# Flasher_LED_Board.net
KiCad netlist of a schematic drawn in EAGLE
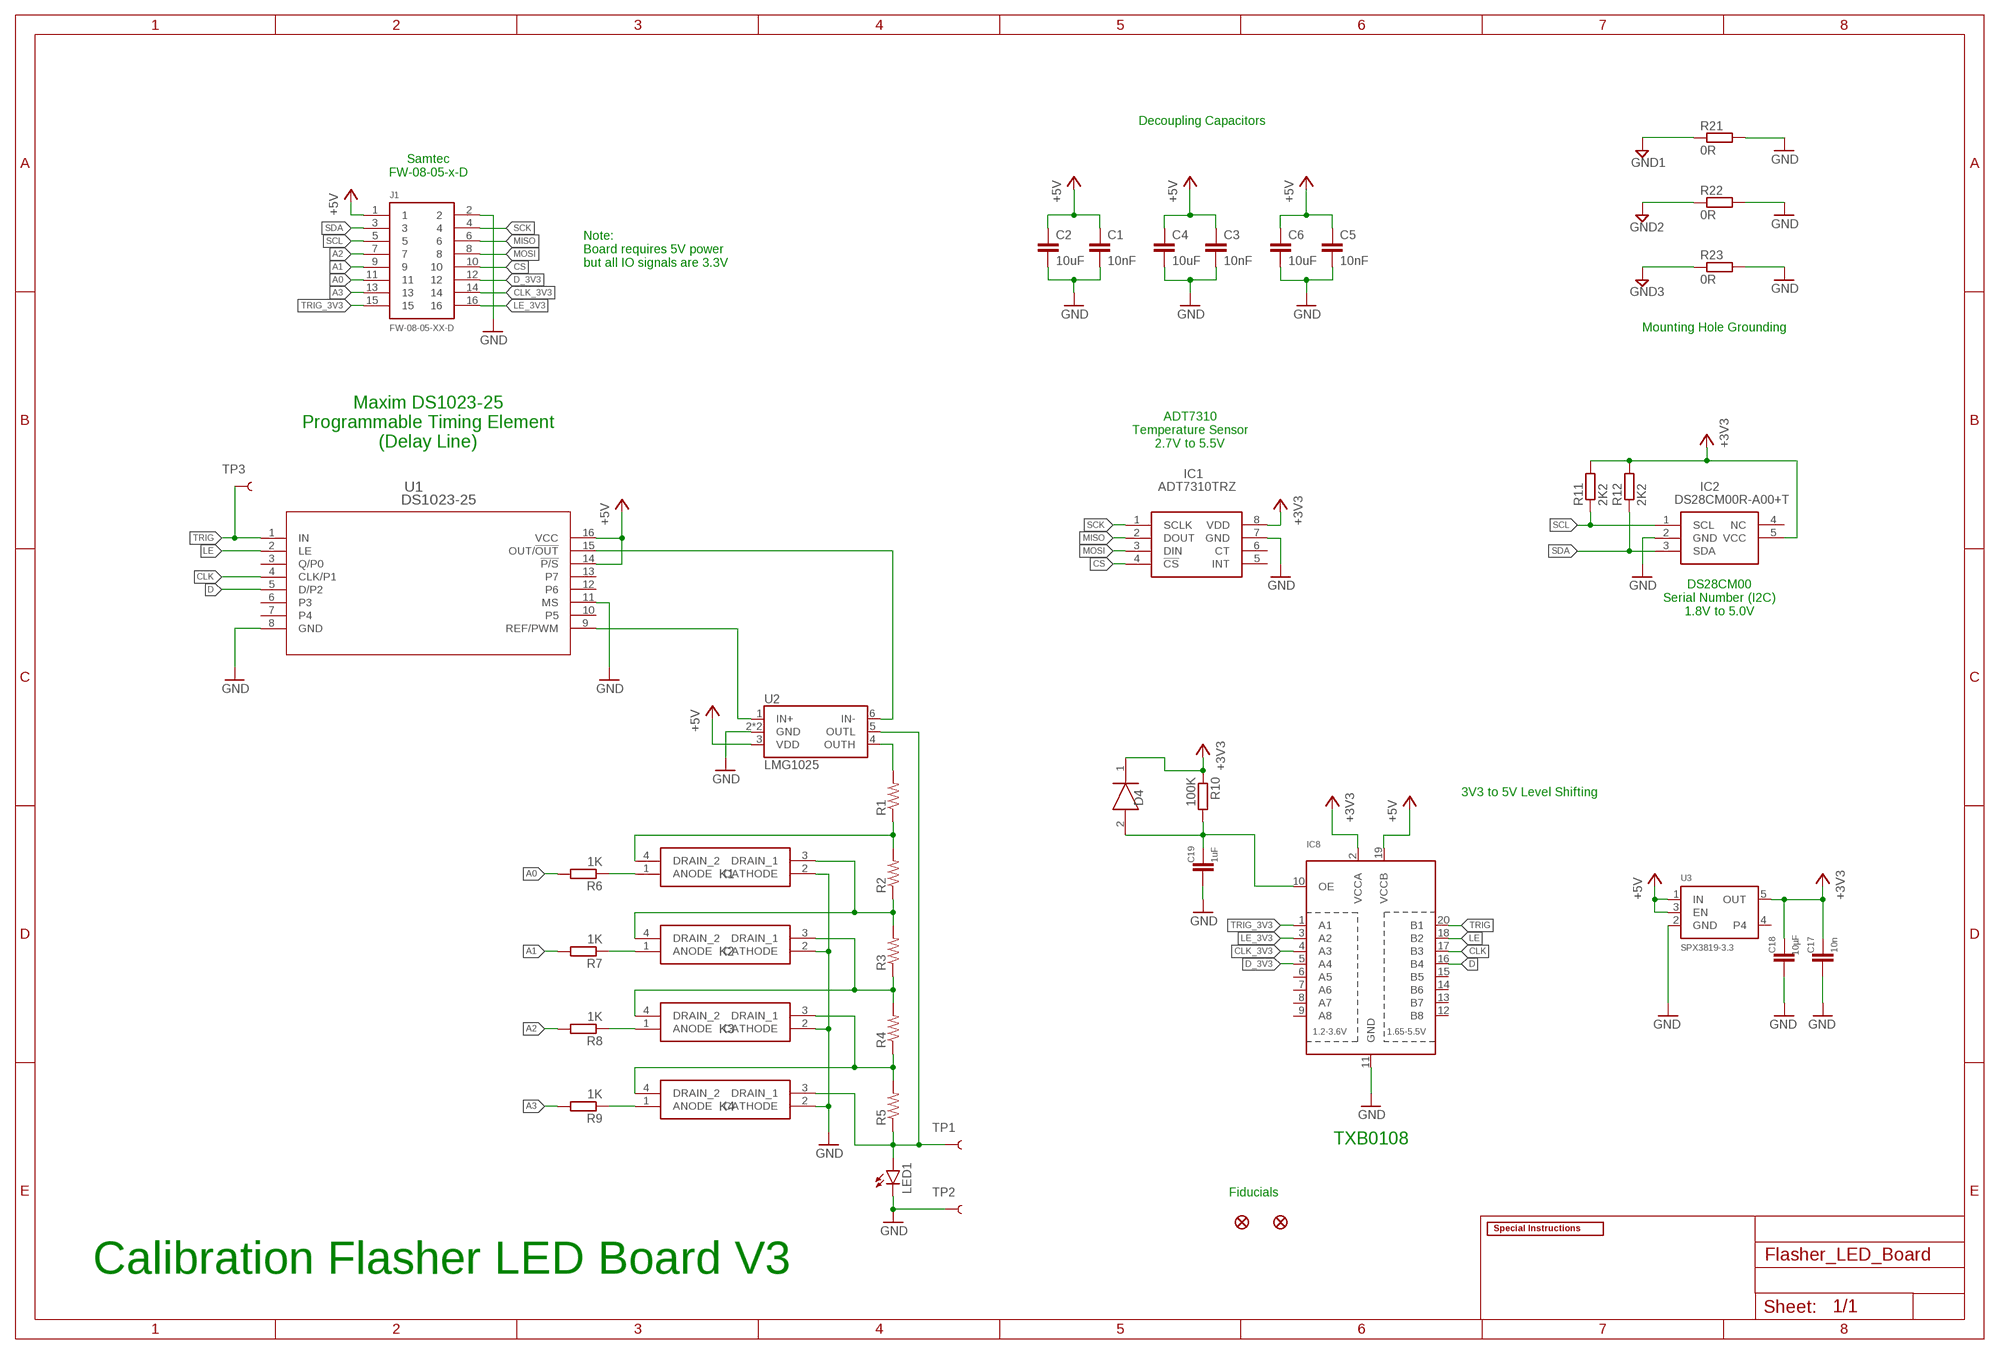
[diagram p0: schematic, sheet 1]

(export (version "E")
  (design (tool "Eeschema 10.0.6"))
  (components
    (comp (ref "C1")
      (value "10nF")
      (footprint "eagle-import:C0805")
      (libsource (lib "eagle-import") (part "C-EUC0805"))
    )
    (comp (ref "C2")
      (value "10uF")
      (footprint "eagle-import:C0805")
      (libsource (lib "eagle-import") (part "C-EUC0805"))
    )
    (comp (ref "C3")
      (value "10nF")
      (footprint "eagle-import:C0805")
      (libsource (lib "eagle-import") (part "C-EUC0805"))
    )
    (comp (ref "C4")
      (value "10uF")
      (footprint "eagle-import:C0805")
      (libsource (lib "eagle-import") (part "C-EUC0805"))
    )
    (comp (ref "C5")
      (value "10nF")
      (footprint "eagle-import:C0805")
      (libsource (lib "eagle-import") (part "C-EUC0805"))
    )
    (comp (ref "C6")
      (value "10uF")
      (footprint "eagle-import:C0805")
      (libsource (lib "eagle-import") (part "C-EUC0805"))
    )
    (comp (ref "C17")
      (value "10n")
      (footprint "eagle-import:C0603")
      (libsource (lib "eagle-import") (part "C-EUC0603"))
    )
    (comp (ref "C18")
      (value "10µF")
      (footprint "eagle-import:C0805")
      (libsource (lib "eagle-import") (part "C-EUC0805"))
    )
    (comp (ref "C19")
      (value "1uF")
      (footprint "eagle-import:C0603")
      (libsource (lib "eagle-import") (part "C-EUC0603"))
    )
    (comp (ref "D4")
      (value "CD0603-B00340")
      (footprint "eagle-import:DIOM179X85N")
      (libsource (lib "eagle-import") (part "CD0603-B00340"))
    )
    (comp (ref "FD1")
      (value "FIDUCIAL1X2")
      (footprint "eagle-import:FIDUCIAL-1X2")
      (libsource (lib "eagle-import") (part "FIDUCIAL1X2"))
    )
    (comp (ref "FD2")
      (value "FIDUCIAL1X2")
      (footprint "eagle-import:FIDUCIAL-1X2")
      (libsource (lib "eagle-import") (part "FIDUCIAL1X2"))
    )
    (comp (ref "IC1")
      (value "ADT7310TRZ")
      (footprint "eagle-import:SOIC127P600X175-8N")
      (fields (field (name "RS_PART_NUMBER") "7969022P"))
      (libsource (lib "eagle-import") (part "ADT7310TRZ"))
    )
    (comp (ref "IC2")
      (value "DS28CM00R-A00+T")
      (footprint "eagle-import:SOT95P280X145-5N")
      (fields (field (name "MOUSER_PART_NUMBER") "700-DS28CM00R-A00T"))
      (libsource (lib "eagle-import") (part "DS28CM00R-A00+T"))
    )
    (comp (ref "IC8")
      (value "TXB0108PWR")
      (footprint "eagle-import:TSSOP20")
      (libsource (lib "eagle-import") (part "TXB0108PWR"))
    )
    (comp (ref "J1")
      (value "FW-08-05-XX-D")
      (footprint "eagle-import:FW-08-05-XX-D")
      (libsource (lib "eagle-import") (part "FW-08-05-XX-D"))
    )
    (comp (ref "K1")
      (value "TLP3475R(TP,F")
      (footprint "eagle-import:TLP3475RTPF")
      (fields (field (name "MOUSER_PART_NUMBER") "757-TLP3475RTPF"))
      (libsource (lib "eagle-import") (part "TLP3475R(TP,F"))
    )
    (comp (ref "K2")
      (value "TLP3475R(TP,F")
      (footprint "eagle-import:TLP3475RTPF")
      (fields (field (name "MOUSER_PART_NUMBER") "757-TLP3475RTPF"))
      (libsource (lib "eagle-import") (part "TLP3475R(TP,F"))
    )
    (comp (ref "K3")
      (value "TLP3475R(TP,F")
      (footprint "eagle-import:TLP3475RTPF")
      (fields (field (name "MOUSER_PART_NUMBER") "757-TLP3475RTPF"))
      (libsource (lib "eagle-import") (part "TLP3475R(TP,F"))
    )
    (comp (ref "K4")
      (value "TLP3475R(TP,F")
      (footprint "eagle-import:TLP3475RTPF")
      (fields (field (name "MOUSER_PART_NUMBER") "757-TLP3475RTPF"))
      (libsource (lib "eagle-import") (part "TLP3475R(TP,F"))
    )
    (comp (ref "LED1")
      (value "LED3MM")
      (footprint "eagle-import:LED3MM")
      (libsource (lib "eagle-import") (part "LED3MM"))
    )
    (comp (ref "LOGO6")
      (value "SPECIAL_INSTRUCTIONS-ORDERING")
      (footprint "eagle-import:ORDERING_INSTRUCTIONS")
      (libsource (lib "eagle-import") (part "SPECIAL_INSTRUCTIONS-ORDERING"))
    )
    (comp (ref "R1")
      (value "RESISTOR0805-RES")
      (footprint "eagle-import:0805")
      (libsource (lib "eagle-import") (part "RESISTOR0805-RES"))
    )
    (comp (ref "R2")
      (value "RESISTOR0805-RES")
      (footprint "eagle-import:0805")
      (libsource (lib "eagle-import") (part "RESISTOR0805-RES"))
    )
    (comp (ref "R3")
      (value "RESISTOR0805-RES")
      (footprint "eagle-import:0805")
      (libsource (lib "eagle-import") (part "RESISTOR0805-RES"))
    )
    (comp (ref "R4")
      (value "RESISTOR0805-RES")
      (footprint "eagle-import:0805")
      (libsource (lib "eagle-import") (part "RESISTOR0805-RES"))
    )
    (comp (ref "R5")
      (value "RESISTOR0805-RES")
      (footprint "eagle-import:0805")
      (libsource (lib "eagle-import") (part "RESISTOR0805-RES"))
    )
    (comp (ref "R6")
      (value "1K")
      (footprint "eagle-import:R0603")
      (libsource (lib "eagle-import") (part "resistor_348_R-EU_R0603"))
    )
    (comp (ref "R7")
      (value "1K")
      (footprint "eagle-import:R0603")
      (libsource (lib "eagle-import") (part "resistor_348_R-EU_R0603"))
    )
    (comp (ref "R8")
      (value "1K")
      (footprint "eagle-import:R0603")
      (libsource (lib "eagle-import") (part "resistor_348_R-EU_R0603"))
    )
    (comp (ref "R9")
      (value "1K")
      (footprint "eagle-import:R0603")
      (libsource (lib "eagle-import") (part "resistor_348_R-EU_R0603"))
    )
    (comp (ref "R10")
      (value "100K")
      (footprint "eagle-import:R0603")
      (libsource (lib "eagle-import") (part "R-EU_R0603"))
    )
    (comp (ref "R11")
      (value "2K2")
      (footprint "eagle-import:R0603")
      (libsource (lib "eagle-import") (part "R-EU_R0603"))
    )
    (comp (ref "R12")
      (value "2K2")
      (footprint "eagle-import:R0603")
      (libsource (lib "eagle-import") (part "R-EU_R0603"))
    )
    (comp (ref "R21")
      (value "0R")
      (footprint "eagle-import:R0603")
      (libsource (lib "eagle-import") (part "R-EU_R0603"))
    )
    (comp (ref "R22")
      (value "0R")
      (footprint "eagle-import:R0603")
      (libsource (lib "eagle-import") (part "R-EU_R0603"))
    )
    (comp (ref "R23")
      (value "0R")
      (footprint "eagle-import:R0603")
      (libsource (lib "eagle-import") (part "R-EU_R0603"))
    )
    (comp (ref "TP1")
      (value "TEST-POINTPOGO_PTH")
      (footprint "eagle-import:1X01_NO_SILK")
      (libsource (lib "eagle-import") (part "TEST-POINTPOGO_PTH"))
    )
    (comp (ref "TP2")
      (value "TEST-POINTPOGO_PTH")
      (footprint "eagle-import:1X01_NO_SILK")
      (libsource (lib "eagle-import") (part "TEST-POINTPOGO_PTH"))
    )
    (comp (ref "TP3")
      (value "TEST-POINTPOGO_PTH")
      (footprint "eagle-import:1X01_NO_SILK")
      (libsource (lib "eagle-import") (part "TEST-POINTPOGO_PTH"))
    )
    (comp (ref "U1")
      (value "DS1023-25")
      (footprint "eagle-import:21-0042B_16")
      (fields (field (name "MANUFACTURER_PART_NUMBER") "DS102325"))
      (libsource (lib "eagle-import") (part "DS1023-25"))
    )
    (comp (ref "U2")
      (value "LMG1025")
      (footprint "eagle-import:LMG1025")
      (libsource (lib "eagle-import") (part "LMG1025"))
    )
    (comp (ref "U3")
      (value "SPX3819-3.3")
      (footprint "eagle-import:SOT23-5")
      (libsource (lib "eagle-import") (part "VREG_SOT23-5"))
    )
  )
  (nets
    (net (code "1") (name "+3V3") (class "Default")
      (node (ref "C17") (pin "1") (pinfunction "1_1") (pintype "passive"))
      (node (ref "C18") (pin "1") (pinfunction "1_1") (pintype "passive"))
      (node (ref "D4") (pin "1") (pinfunction "K_1") (pintype "bidirectional"))
      (node (ref "IC1") (pin "8") (pinfunction "VDD_8") (pintype "power_in"))
      (node (ref "IC2") (pin "5") (pinfunction "VCC_5") (pintype "bidirectional"))
      (node (ref "IC8") (pin "2") (pinfunction "VCCA_2") (pintype "bidirectional"))
      (node (ref "R10") (pin "1") (pinfunction "1_1") (pintype "passive"))
      (node (ref "R11") (pin "2") (pinfunction "2_2") (pintype "passive"))
      (node (ref "R12") (pin "2") (pinfunction "2_2") (pintype "passive"))
      (node (ref "U3") (pin "5") (pinfunction "OUT_5") (pintype "power_in"))
    )
    (net (code "2") (name "+5V") (class "Default")
      (node (ref "C1") (pin "1") (pinfunction "1_1") (pintype "passive"))
      (node (ref "C2") (pin "1") (pinfunction "1_1") (pintype "passive"))
      (node (ref "C3") (pin "1") (pinfunction "1_1") (pintype "passive"))
      (node (ref "C4") (pin "1") (pinfunction "1_1") (pintype "passive"))
      (node (ref "C5") (pin "1") (pinfunction "1_1") (pintype "passive"))
      (node (ref "C6") (pin "1") (pinfunction "1_1") (pintype "passive"))
      (node (ref "IC8") (pin "19") (pinfunction "VCCB_19") (pintype "bidirectional"))
      (node (ref "J1") (pin "1") (pinfunction "1_1") (pintype "bidirectional"))
      (node (ref "U1") (pin "14") (pinfunction "~{P/S}_14") (pintype "passive"))
      (node (ref "U1") (pin "16") (pinfunction "VCC_16") (pintype "power_in"))
      (node (ref "U2") (pin "3") (pinfunction "VDD_3") (pintype "power_in"))
      (node (ref "U3") (pin "1") (pinfunction "IN_1") (pintype "power_in"))
      (node (ref "U3") (pin "3") (pinfunction "EN_3") (pintype "input"))
    )
    (net (code "3") (name "A0") (class "Default")
      (node (ref "J1") (pin "11") (pinfunction "11_11") (pintype "bidirectional"))
      (node (ref "R6") (pin "2") (pinfunction "2_2") (pintype "passive"))
    )
    (net (code "4") (name "A1") (class "Default")
      (node (ref "J1") (pin "9") (pinfunction "9_9") (pintype "bidirectional"))
      (node (ref "R7") (pin "2") (pinfunction "2_2") (pintype "passive"))
    )
    (net (code "5") (name "A2") (class "Default")
      (node (ref "J1") (pin "7") (pinfunction "7_7") (pintype "bidirectional"))
      (node (ref "R8") (pin "2") (pinfunction "2_2") (pintype "passive"))
    )
    (net (code "6") (name "A3") (class "Default")
      (node (ref "J1") (pin "13") (pinfunction "13_13") (pintype "bidirectional"))
      (node (ref "R9") (pin "2") (pinfunction "2_2") (pintype "passive"))
    )
    (net (code "7") (name "CLK") (class "Default")
      (node (ref "IC8") (pin "17") (pinfunction "B3_17") (pintype "bidirectional"))
      (node (ref "U1") (pin "4") (pinfunction "CLK/P1_4") (pintype "passive"))
    )
    (net (code "8") (name "CLK_3V3") (class "Default")
      (node (ref "IC8") (pin "4") (pinfunction "A3_4") (pintype "bidirectional"))
      (node (ref "J1") (pin "14") (pinfunction "14_14") (pintype "bidirectional"))
    )
    (net (code "9") (name "CS") (class "Default")
      (node (ref "IC1") (pin "4") (pinfunction "~{CS}_4") (pintype "input"))
      (node (ref "J1") (pin "10") (pinfunction "10_10") (pintype "bidirectional"))
    )
    (net (code "10") (name "D") (class "Default")
      (node (ref "IC8") (pin "16") (pinfunction "B4_16") (pintype "bidirectional"))
      (node (ref "U1") (pin "5") (pinfunction "D/P2_5") (pintype "passive"))
    )
    (net (code "11") (name "D_3V3") (class "Default")
      (node (ref "IC8") (pin "5") (pinfunction "A4_5") (pintype "bidirectional"))
      (node (ref "J1") (pin "12") (pinfunction "12_12") (pintype "bidirectional"))
    )
    (net (code "12") (name "GND") (class "Default")
      (node (ref "C1") (pin "2") (pinfunction "2_2") (pintype "passive"))
      (node (ref "C17") (pin "2") (pinfunction "2_2") (pintype "passive"))
      (node (ref "C18") (pin "2") (pinfunction "2_2") (pintype "passive"))
      (node (ref "C19") (pin "2") (pinfunction "2_2") (pintype "passive"))
      (node (ref "C2") (pin "2") (pinfunction "2_2") (pintype "passive"))
      (node (ref "C3") (pin "2") (pinfunction "2_2") (pintype "passive"))
      (node (ref "C4") (pin "2") (pinfunction "2_2") (pintype "passive"))
      (node (ref "C5") (pin "2") (pinfunction "2_2") (pintype "passive"))
      (node (ref "C6") (pin "2") (pinfunction "2_2") (pintype "passive"))
      (node (ref "IC1") (pin "7") (pinfunction "GND_7") (pintype "power_in"))
      (node (ref "IC2") (pin "2") (pinfunction "GND_2") (pintype "bidirectional"))
      (node (ref "IC8") (pin "11") (pinfunction "GND_11") (pintype "bidirectional"))
      (node (ref "J1") (pin "2") (pinfunction "2_2") (pintype "bidirectional"))
      (node (ref "K1") (pin "2") (pinfunction "CATHODE_2") (pintype "bidirectional"))
      (node (ref "K2") (pin "2") (pinfunction "CATHODE_2") (pintype "bidirectional"))
      (node (ref "K3") (pin "2") (pinfunction "CATHODE_2") (pintype "bidirectional"))
      (node (ref "K4") (pin "2") (pinfunction "CATHODE_2") (pintype "bidirectional"))
      (node (ref "LED1") (pin "K") (pinfunction "C_K") (pintype "passive"))
      (node (ref "R21") (pin "2") (pinfunction "2_2") (pintype "passive"))
      (node (ref "R22") (pin "2") (pinfunction "2_2") (pintype "passive"))
      (node (ref "R23") (pin "2") (pinfunction "2_2") (pintype "passive"))
      (node (ref "TP2") (pin "1") (pinfunction "1_1") (pintype "bidirectional"))
      (node (ref "U1") (pin "11") (pinfunction "MS_11") (pintype "passive"))
      (node (ref "U1") (pin "8") (pinfunction "GND_8") (pintype "power_in"))
      (node (ref "U2") (pin "2") (pinfunction "GND_2") (pintype "power_in"))
      (node (ref "U2") (pin "PAD") (pinfunction "GND_PAD") (pintype "power_in"))
      (node (ref "U3") (pin "2") (pinfunction "GND_2") (pintype "power_in"))
    )
    (net (code "13") (name "GND1") (class "Default")
      (node (ref "R21") (pin "1") (pinfunction "1_1") (pintype "passive"))
    )
    (net (code "14") (name "GND2") (class "Default")
      (node (ref "R22") (pin "1") (pinfunction "1_1") (pintype "passive"))
    )
    (net (code "15") (name "GND3") (class "Default")
      (node (ref "R23") (pin "1") (pinfunction "1_1") (pintype "passive"))
    )
    (net (code "16") (name "LE") (class "Default")
      (node (ref "IC8") (pin "18") (pinfunction "B2_18") (pintype "bidirectional"))
      (node (ref "U1") (pin "2") (pinfunction "LE_2") (pintype "passive"))
    )
    (net (code "17") (name "LE_3V3") (class "Default")
      (node (ref "IC8") (pin "3") (pinfunction "A2_3") (pintype "bidirectional"))
      (node (ref "J1") (pin "16") (pinfunction "16_16") (pintype "bidirectional"))
    )
    (net (code "18") (name "MISO") (class "Default")
      (node (ref "IC1") (pin "2") (pinfunction "DOUT_2") (pintype "output"))
      (node (ref "J1") (pin "6") (pinfunction "6_6") (pintype "bidirectional"))
    )
    (net (code "19") (name "MOSI") (class "Default")
      (node (ref "IC1") (pin "3") (pinfunction "DIN_3") (pintype "input"))
      (node (ref "J1") (pin "8") (pinfunction "8_8") (pintype "bidirectional"))
    )
    (net (code "20") (name "Net-(D4-A)") (class "Default")
      (node (ref "C19") (pin "1") (pinfunction "1_1") (pintype "passive"))
      (node (ref "D4") (pin "2") (pinfunction "A_2") (pintype "bidirectional"))
      (node (ref "IC8") (pin "10") (pinfunction "OE_10") (pintype "bidirectional"))
      (node (ref "R10") (pin "2") (pinfunction "2_2") (pintype "passive"))
    )
    (net (code "21") (name "Net-(K1-ANODE)") (class "Default")
      (node (ref "K1") (pin "1") (pinfunction "ANODE_1") (pintype "bidirectional"))
      (node (ref "R6") (pin "1") (pinfunction "1_1") (pintype "passive"))
    )
    (net (code "22") (name "Net-(K1-DRAIN_1)") (class "Default")
      (node (ref "K1") (pin "3") (pinfunction "DRAIN_1_3") (pintype "bidirectional"))
      (node (ref "K2") (pin "4") (pinfunction "DRAIN_2_4") (pintype "bidirectional"))
      (node (ref "R2") (pin "1") (pinfunction "1_1") (pintype "passive"))
      (node (ref "R3") (pin "2") (pinfunction "2_2") (pintype "passive"))
    )
    (net (code "23") (name "Net-(K1-DRAIN_2)") (class "Default")
      (node (ref "K1") (pin "4") (pinfunction "DRAIN_2_4") (pintype "bidirectional"))
      (node (ref "R1") (pin "1") (pinfunction "1_1") (pintype "passive"))
      (node (ref "R2") (pin "2") (pinfunction "2_2") (pintype "passive"))
    )
    (net (code "24") (name "Net-(K2-ANODE)") (class "Default")
      (node (ref "K2") (pin "1") (pinfunction "ANODE_1") (pintype "bidirectional"))
      (node (ref "R7") (pin "1") (pinfunction "1_1") (pintype "passive"))
    )
    (net (code "25") (name "Net-(K2-DRAIN_1)") (class "Default")
      (node (ref "K2") (pin "3") (pinfunction "DRAIN_1_3") (pintype "bidirectional"))
      (node (ref "K3") (pin "4") (pinfunction "DRAIN_2_4") (pintype "bidirectional"))
      (node (ref "R3") (pin "1") (pinfunction "1_1") (pintype "passive"))
      (node (ref "R4") (pin "2") (pinfunction "2_2") (pintype "passive"))
    )
    (net (code "26") (name "Net-(K3-ANODE)") (class "Default")
      (node (ref "K3") (pin "1") (pinfunction "ANODE_1") (pintype "bidirectional"))
      (node (ref "R8") (pin "1") (pinfunction "1_1") (pintype "passive"))
    )
    (net (code "27") (name "Net-(K3-DRAIN_1)") (class "Default")
      (node (ref "K3") (pin "3") (pinfunction "DRAIN_1_3") (pintype "bidirectional"))
      (node (ref "K4") (pin "4") (pinfunction "DRAIN_2_4") (pintype "bidirectional"))
      (node (ref "R4") (pin "1") (pinfunction "1_1") (pintype "passive"))
      (node (ref "R5") (pin "2") (pinfunction "2_2") (pintype "passive"))
    )
    (net (code "28") (name "Net-(K4-ANODE)") (class "Default")
      (node (ref "K4") (pin "1") (pinfunction "ANODE_1") (pintype "bidirectional"))
      (node (ref "R9") (pin "1") (pinfunction "1_1") (pintype "passive"))
    )
    (net (code "29") (name "Net-(K4-DRAIN_1)") (class "Default")
      (node (ref "K4") (pin "3") (pinfunction "DRAIN_1_3") (pintype "bidirectional"))
      (node (ref "LED1") (pin "A") (pinfunction "A_A") (pintype "passive"))
      (node (ref "R5") (pin "1") (pinfunction "1_1") (pintype "passive"))
      (node (ref "TP1") (pin "1") (pinfunction "1_1") (pintype "bidirectional"))
      (node (ref "U2") (pin "5") (pinfunction "OUTL_5") (pintype "output"))
    )
    (net (code "30") (name "Net-(U1-OUT{slash}~{OUT})") (class "Default")
      (node (ref "U1") (pin "15") (pinfunction "OUT/~{OUT}_15") (pintype "passive"))
      (node (ref "U2") (pin "6") (pinfunction "IN-_6") (pintype "input"))
    )
    (net (code "31") (name "Net-(U1-REF{slash}PWM)") (class "Default")
      (node (ref "U1") (pin "9") (pinfunction "REF/PWM_9") (pintype "passive"))
      (node (ref "U2") (pin "1") (pinfunction "IN+_1") (pintype "input"))
    )
    (net (code "32") (name "Net-(U2-OUTH)") (class "Default")
      (node (ref "R1") (pin "2") (pinfunction "2_2") (pintype "passive"))
      (node (ref "U2") (pin "4") (pinfunction "OUTH_4") (pintype "output"))
    )
    (net (code "33") (name "SCK") (class "Default")
      (node (ref "IC1") (pin "1") (pinfunction "SCLK_1") (pintype "input"))
      (node (ref "J1") (pin "4") (pinfunction "4_4") (pintype "bidirectional"))
    )
    (net (code "34") (name "SCL") (class "Default")
      (node (ref "IC2") (pin "1") (pinfunction "SCL_1") (pintype "bidirectional"))
      (node (ref "J1") (pin "5") (pinfunction "5_5") (pintype "bidirectional"))
      (node (ref "R11") (pin "1") (pinfunction "1_1") (pintype "passive"))
    )
    (net (code "35") (name "SDA") (class "Default")
      (node (ref "IC2") (pin "3") (pinfunction "SDA_3") (pintype "bidirectional"))
      (node (ref "J1") (pin "3") (pinfunction "3_3") (pintype "bidirectional"))
      (node (ref "R12") (pin "1") (pinfunction "1_1") (pintype "passive"))
    )
    (net (code "36") (name "TRIG") (class "Default")
      (node (ref "IC8") (pin "20") (pinfunction "B1_20") (pintype "bidirectional"))
      (node (ref "TP3") (pin "1") (pinfunction "1_1") (pintype "bidirectional"))
      (node (ref "U1") (pin "1") (pinfunction "IN_1") (pintype "input"))
    )
    (net (code "37") (name "TRIG_3V3") (class "Default")
      (node (ref "IC8") (pin "1") (pinfunction "A1_1") (pintype "bidirectional"))
      (node (ref "J1") (pin "15") (pinfunction "15_15") (pintype "bidirectional"))
    )
    (net (code "38") (name "unconnected-(IC1-CT-Pad6)") (class "Default")
      (node (ref "IC1") (pin "6") (pinfunction "CT_6") (pintype "bidirectional"))
    )
    (net (code "39") (name "unconnected-(IC1-INT-Pad5)") (class "Default")
      (node (ref "IC1") (pin "5") (pinfunction "INT_5") (pintype "input"))
    )
    (net (code "40") (name "unconnected-(IC2-NC-Pad4)") (class "Default")
      (node (ref "IC2") (pin "4") (pinfunction "NC_4") (pintype "no_connect"))
    )
    (net (code "41") (name "unconnected-(IC8-A5-Pad6)") (class "Default")
      (node (ref "IC8") (pin "6") (pinfunction "A5_6") (pintype "bidirectional"))
    )
    (net (code "42") (name "unconnected-(IC8-A6-Pad7)") (class "Default")
      (node (ref "IC8") (pin "7") (pinfunction "A6_7") (pintype "bidirectional"))
    )
    (net (code "43") (name "unconnected-(IC8-A7-Pad8)") (class "Default")
      (node (ref "IC8") (pin "8") (pinfunction "A7_8") (pintype "bidirectional"))
    )
    (net (code "44") (name "unconnected-(IC8-A8-Pad9)") (class "Default")
      (node (ref "IC8") (pin "9") (pinfunction "A8_9") (pintype "bidirectional"))
    )
    (net (code "45") (name "unconnected-(IC8-B5-Pad15)") (class "Default")
      (node (ref "IC8") (pin "15") (pinfunction "B5_15") (pintype "bidirectional"))
    )
    (net (code "46") (name "unconnected-(IC8-B6-Pad14)") (class "Default")
      (node (ref "IC8") (pin "14") (pinfunction "B6_14") (pintype "bidirectional"))
    )
    (net (code "47") (name "unconnected-(IC8-B7-Pad13)") (class "Default")
      (node (ref "IC8") (pin "13") (pinfunction "B7_13") (pintype "bidirectional"))
    )
    (net (code "48") (name "unconnected-(IC8-B8-Pad12)") (class "Default")
      (node (ref "IC8") (pin "12") (pinfunction "B8_12") (pintype "bidirectional"))
    )
    (net (code "49") (name "unconnected-(U1-P3-Pad6)") (class "Default")
      (node (ref "U1") (pin "6") (pinfunction "P3_6") (pintype "passive"))
    )
    (net (code "50") (name "unconnected-(U1-P4-Pad7)") (class "Default")
      (node (ref "U1") (pin "7") (pinfunction "P4_7") (pintype "passive"))
    )
    (net (code "51") (name "unconnected-(U1-P5-Pad10)") (class "Default")
      (node (ref "U1") (pin "10") (pinfunction "P5_10") (pintype "passive"))
    )
    (net (code "52") (name "unconnected-(U1-P6-Pad12)") (class "Default")
      (node (ref "U1") (pin "12") (pinfunction "P6_12") (pintype "passive"))
    )
    (net (code "53") (name "unconnected-(U1-P7-Pad13)") (class "Default")
      (node (ref "U1") (pin "13") (pinfunction "P7_13") (pintype "passive"))
    )
    (net (code "54") (name "unconnected-(U1-Q{slash}P0-Pad3)") (class "Default")
      (node (ref "U1") (pin "3") (pinfunction "Q/P0_3") (pintype "passive"))
    )
    (net (code "55") (name "unconnected-(U3-P4-Pad4)") (class "Default")
      (node (ref "U3") (pin "4") (pinfunction "P4_4") (pintype "bidirectional"))
    )
  )
)
